# MISC.net
KiCad netlist of a schematic drawn in Altium Designer
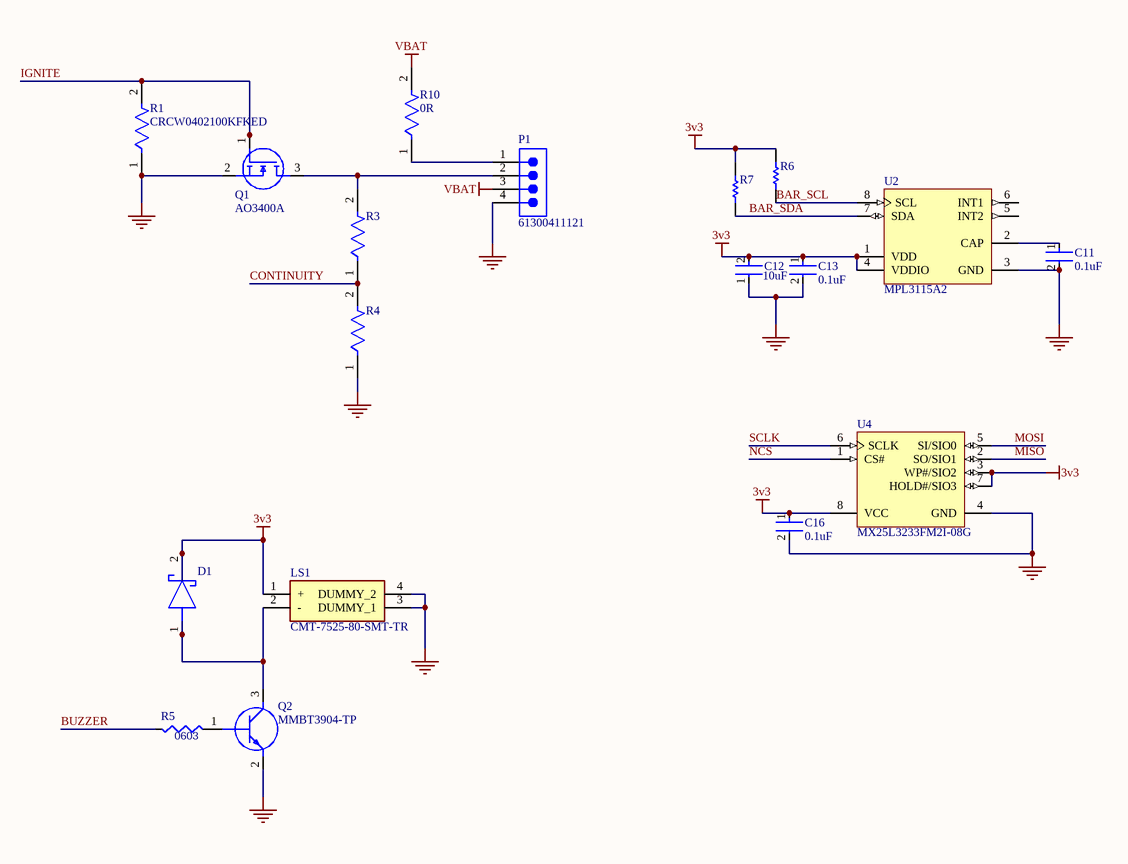
[diagram p0: MISC.SchDoc]

(export (version "E")
  (design (tool "Eeschema 10.0.6"))
  (components
    (comp (ref "C11")
      (value "0.1uF")
      (footprint "FP-C0402-BB-MFG")
      (description "CAP CER 0.1UF 10V X5R 0402")
      (fields (field (name "MANUFACTURER") "Kemet") (field (name "TOLERANCE") "0.1"))
      (libsource (lib "Altium Content Vault") (part "b4654b650e69147ec39a6b967a45e02"))
    )
    (comp (ref "C12")
      (value "10uF")
      (footprint "FP-C1608-080-0_1-MFG")
      (description "Multilayer Ceramic Capacitors 10μF ±10% 10V X5R SMD 0603")
      (fields (field (name "VOLTAGE") "10V") (field (name "TOLERANCE") "10%"))
      (libsource (lib "Altium Content Vault") (part "236180d848d6139a670b325ea6854c9"))
    )
    (comp (ref "C13")
      (value "0.1uF")
      (footprint "FP-C0402-BB-MFG")
      (description "CAP CER 0.1UF 10V X5R 0402")
      (fields (field (name "MANUFACTURER") "Kemet") (field (name "TOLERANCE") "0.1"))
      (libsource (lib "Altium Content Vault") (part "b4654b650e69147ec39a6b967a45e02"))
    )
    (comp (ref "C16")
      (value "0.1uF")
      (footprint "FP-C0402-BB-MFG")
      (description "CAP CER 0.1UF 10V X5R 0402")
      (fields (field (name "MANUFACTURER") "Kemet") (field (name "TOLERANCE") "0.1"))
      (libsource (lib "Altium Content Vault") (part "b4654b650e69147ec39a6b967a45e02"))
    )
    (comp (ref "D1")
      (value "RB161QS-40T18R")
      (footprint "SamacSys:RB161QS40T18R")
      (description "Schottky Diode")
      (fields (field (name "MOUSER PART NUMBER") "755-RB161QS-40T18R"))
      (libsource (lib "*") (part "RB161QS-40T18R"))
    )
    (comp (ref "LS1")
      (value "CMT-7525-80-SMT-TR")
      (footprint "SamacSys:CMT752580SMTTR")
      (description "Loudspeaker or Buzzer")
      (fields (field (name "MOUSER PART NUMBER") "490-CMT-7525-80SMTTR"))
      (libsource (lib "*") (part "CMT-7525-80-SMT-TR"))
    )
    (comp (ref "P1")
      (value "61300411121")
      (footprint "61300411121")
      (libsource (lib "Altium Content Vault") (part "Header_Male_1R_04P"))
    )
    (comp (ref "Q1")
      (value "AO3400A")
      (footprint "SamacSys:SOT95P280X125-3N")
      (description "MOSFET (N-Channel)")
      (libsource (lib "*") (part "AO3400A"))
    )
    (comp (ref "Q2")
      (value "MMBT3904-TP")
      (footprint "SamacSys:SOT95P237X125-3N")
      (description "Transistor BJT NPN")
      (fields (field (name "MOUSER PART NUMBER") "833-MMBT3904-TP"))
      (libsource (lib "*") (part "MMBT3904-TP"))
    )
    (comp (ref "R1")
      (value "CRCW0402100KFKED")
      (footprint "FP-CRCW0402-e3-IPC_C")
      (description "RES Thick Film, 100kΩ, 1%, 0.063W, 100ppm/°C, 0402")
      (fields (field (name "TOLERANCE") "1%"))
      (libsource (lib "Altium Content Vault") (part "1029c3af85768c4190bb7ad29bc67b5"))
    )
    (comp (ref "R3")
      (value "CRCW0402100KFKED")
      (footprint "FP-CRCW0402-e3-IPC_C")
      (description "RES Thick Film, 100kΩ, 1%, 0.063W, 100ppm/°C, 0402")
      (fields (field (name "TOLERANCE") "1%"))
      (libsource (lib "Altium Content Vault") (part "1029c3af85768c4190bb7ad29bc67b5"))
    )
    (comp (ref "R4")
      (value "CRCW040250K0FKED")
      (footprint "FP-CRCW0402-e3-IPC_A")
      (description "RES Thick Film, 50kΩ, 1%, 0.063W, 100ppm/°C, 0402")
      (fields (field (name "TOLERANCE") "1%"))
      (libsource (lib "Altium Content Vault") (part "1029c3af85768c4190bb7ad29bc67b5"))
    )
    (comp (ref "R5")
      (value "ERJ-3EKF2000V")
      (footprint "R0603")
      (description "200 OHM 1% 1/10W 0603")
      (fields (field (name "MADE BY") "Brennan Swanton") (field (name "REVIEWED BY") "*"))
      (libsource (lib "USCRPL") (part "Symbol"))
    )
    (comp (ref "R6")
      (value "RC0402JR-074K7L")
      (footprint "RESC1005X40X25LL05T10")
      (fields (field (name "MANUFACTURER") "Yageo / Phycomp"))
      (libsource (lib "Altium Content Vault") (part "RES"))
    )
    (comp (ref "R7")
      (value "RC0402JR-074K7L")
      (footprint "RESC1005X40X25LL05T10")
      (fields (field (name "MANUFACTURER") "Yageo / Phycomp"))
      (libsource (lib "Altium Content Vault") (part "RES"))
    )
    (comp (ref "R10")
      (value "0R")
      (footprint "FP-RK73Z1J-MFG")
      (description "RES 0 OHM JUMPER 0603")
      (fields (field (name "TOLERANCE") "1%"))
      (libsource (lib "Altium Content Vault") (part "1029c3af85768c4190bb7ad29bc67b5"))
    )
    (comp (ref "U2")
      (value "MPL3115A2")
      (footprint "FRES-2153-01_V")
      (description "Xtrinsic I2C Precision Altimeter, 1.95 to 3.6 V, -40 to 85 degC, 8-Pin LGA (2153-01), RoHS, Tray")
      (fields (field (name "MANUFACTURER") "Freescale Semiconductor"))
      (libsource (lib "Altium Content Vault") (part "FRES-MPL3115A2-8"))
    )
    (comp (ref "U4")
      (value "MX25L3233FM2I-08G")
      (footprint "MXIC-SOP-8_M")
      (fields (field (name "MANUFACTURER") "Macronix"))
      (libsource (lib "Altium Content Vault") (part "MXIC-MX25L3233FM2I-08G-SOP-8"))
    )
  )
  (nets
    (net (code "1") (name "/BAR_SCL") (class "Default")
      (node (ref "R6") (pin "1") (pinfunction "1_1") (pintype "passive"))
      (node (ref "U2") (pin "8") (pinfunction "SCL_8") (pintype "input"))
    )
    (net (code "2") (name "/BAR_SDA") (class "Default")
      (node (ref "R7") (pin "1") (pinfunction "1_1") (pintype "passive"))
      (node (ref "U2") (pin "7") (pinfunction "SDA_7") (pintype "bidirectional"))
    )
    (net (code "3") (name "/BUZZER") (class "Default")
      (node (ref "R5") (pin "1") (pinfunction "1_1") (pintype "passive"))
    )
    (net (code "4") (name "/CONTINUITY") (class "Default")
      (node (ref "R3") (pin "1") (pinfunction "1_1") (pintype "passive"))
      (node (ref "R4") (pin "2") (pinfunction "2_2") (pintype "passive"))
    )
    (net (code "5") (name "/IGNITE") (class "Default")
      (node (ref "Q1") (pin "1") (pinfunction "G_1") (pintype "passive"))
      (node (ref "R1") (pin "2") (pinfunction "2_2") (pintype "passive"))
    )
    (net (code "6") (name "/MISO") (class "Default")
      (node (ref "U4") (pin "2") (pinfunction "SO/SIO1_2") (pintype "bidirectional"))
    )
    (net (code "7") (name "/MOSI") (class "Default")
      (node (ref "U4") (pin "5") (pinfunction "SI/SIO0_5") (pintype "bidirectional"))
    )
    (net (code "8") (name "/NCS") (class "Default")
      (node (ref "U4") (pin "1") (pinfunction "CS#_1") (pintype "input"))
    )
    (net (code "9") (name "/SCLK") (class "Default")
      (node (ref "U4") (pin "6") (pinfunction "SCLK_6") (pintype "input"))
    )
    (net (code "10") (name "3v3") (class "Default")
      (node (ref "C12") (pin "2") (pinfunction "2_2") (pintype "passive"))
      (node (ref "C13") (pin "1") (pinfunction "1_1") (pintype "passive"))
      (node (ref "C16") (pin "1") (pinfunction "1_1") (pintype "passive"))
      (node (ref "D1") (pin "2") (pinfunction "K_2") (pintype "passive"))
      (node (ref "LS1") (pin "1") (pinfunction "+_1") (pintype "passive"))
      (node (ref "R6") (pin "2") (pinfunction "2_2") (pintype "passive"))
      (node (ref "R7") (pin "2") (pinfunction "2_2") (pintype "passive"))
      (node (ref "U2") (pin "1") (pinfunction "VDD_1") (pintype "power_in"))
      (node (ref "U2") (pin "4") (pinfunction "VDDIO_4") (pintype "power_in"))
      (node (ref "U4") (pin "3") (pinfunction "WP#/SIO2_3") (pintype "bidirectional"))
      (node (ref "U4") (pin "7") (pinfunction "HOLD#/SIO3_7") (pintype "bidirectional"))
      (node (ref "U4") (pin "8") (pinfunction "VCC_8") (pintype "power_in"))
    )
    (net (code "11") (name "GND") (class "Default")
      (node (ref "C11") (pin "2") (pinfunction "2_2") (pintype "passive"))
      (node (ref "C12") (pin "1") (pinfunction "1_1") (pintype "passive"))
      (node (ref "C13") (pin "2") (pinfunction "2_2") (pintype "passive"))
      (node (ref "C16") (pin "2") (pinfunction "2_2") (pintype "passive"))
      (node (ref "LS1") (pin "3") (pinfunction "DUMMY_1_3") (pintype "passive"))
      (node (ref "LS1") (pin "4") (pinfunction "DUMMY_2_4") (pintype "passive"))
      (node (ref "P1") (pin "4") (pinfunction "4_4") (pintype "passive"))
      (node (ref "Q1") (pin "2") (pinfunction "S_2") (pintype "passive"))
      (node (ref "Q2") (pin "2") (pinfunction "E_2") (pintype "passive"))
      (node (ref "R1") (pin "1") (pinfunction "1_1") (pintype "passive"))
      (node (ref "R4") (pin "1") (pinfunction "1_1") (pintype "passive"))
      (node (ref "U2") (pin "3") (pinfunction "GND_3") (pintype "power_in"))
      (node (ref "U4") (pin "4") (pinfunction "GND_4") (pintype "power_in"))
    )
    (net (code "12") (name "Net-(D1-A)") (class "Default")
      (node (ref "D1") (pin "1") (pinfunction "A_1") (pintype "passive"))
      (node (ref "LS1") (pin "2") (pinfunction "-_2") (pintype "passive"))
      (node (ref "Q2") (pin "3") (pinfunction "C_3") (pintype "passive"))
    )
    (net (code "13") (name "Net-(P1-Pad1)") (class "Default")
      (node (ref "P1") (pin "1") (pinfunction "1_1") (pintype "passive"))
      (node (ref "R10") (pin "1") (pinfunction "1_1") (pintype "passive"))
    )
    (net (code "14") (name "Net-(Q1-D)") (class "Default")
      (node (ref "P1") (pin "2") (pinfunction "2_2") (pintype "passive"))
      (node (ref "Q1") (pin "3") (pinfunction "D_3") (pintype "passive"))
      (node (ref "R3") (pin "2") (pinfunction "2_2") (pintype "passive"))
    )
    (net (code "15") (name "Net-(Q2-B)") (class "Default")
      (node (ref "Q2") (pin "1") (pinfunction "B_1") (pintype "passive"))
      (node (ref "R5") (pin "2") (pinfunction "2_2") (pintype "passive"))
    )
    (net (code "16") (name "Net-(U2-CAP)") (class "Default")
      (node (ref "C11") (pin "1") (pinfunction "1_1") (pintype "passive"))
      (node (ref "U2") (pin "2") (pinfunction "CAP_2") (pintype "passive"))
    )
    (net (code "17") (name "VBAT") (class "Default")
      (node (ref "P1") (pin "3") (pinfunction "3_3") (pintype "passive"))
      (node (ref "R10") (pin "2") (pinfunction "2_2") (pintype "passive"))
    )
    (net (code "18") (name "unconnected-(U2-INT1-Pad6)") (class "Default")
      (node (ref "U2") (pin "6") (pinfunction "INT1_6") (pintype "output"))
    )
    (net (code "19") (name "unconnected-(U2-INT2-Pad5)") (class "Default")
      (node (ref "U2") (pin "5") (pinfunction "INT2_5") (pintype "output"))
    )
  )
)
